# GPS_-_ML8088s.net
KiCad netlist of a schematic drawn in Altium Designer
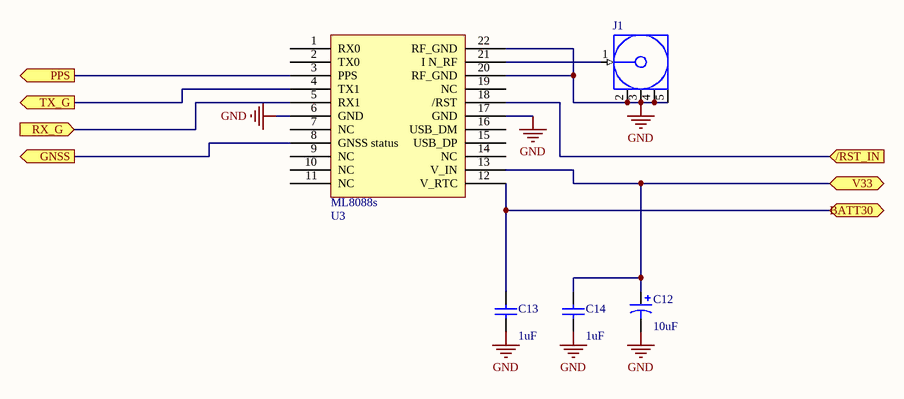
[diagram p0: GPS - ML8088s.SchDoc]

(export (version "E")
  (design (tool "Eeschema 10.0.6"))
  (components
    (comp (ref "C12")
      (value "10uF")
      (footprint "R38")
      (description "Polarized Capacitor (Radial)")
      (fields (field (name "Comment") "Cap Pol1") (field (name "PUBLISHER") "Altium Limited"))
      (libsource (lib "Miscellaneous Devices") (part "Cap Pol1"))
    )
    (comp (ref "C13")
      (value "1uF")
      (footprint "RAD-0.1")
      (description "Capacitor")
      (fields (field (name "Comment") "Cap") (field (name "PUBLISHER") "Altium Limited"))
      (libsource (lib "Miscellaneous Devices") (part "Cap"))
    )
    (comp (ref "C14")
      (value "1uF")
      (footprint "RAD-0.1")
      (description "Capacitor")
      (fields (field (name "Comment") "Cap") (field (name "PUBLISHER") "Altium Limited"))
      (libsource (lib "Miscellaneous Devices") (part "Cap"))
    )
    (comp (ref "J1")
      (value "COAX-F")
      (footprint "MCX5.08-H5")
      (fields (field (name "PUBLISHER") "Altium Limited"))
      (libsource (lib "Miscellaneous Connectors") (part "COAX-F"))
    )
    (comp (ref "U3")
      (value "Component_1")
      (footprint "LCCS127P1300X1500X280-22M")
      (libsource (lib "gps&gsm") (part "Component_1"))
    )
  )
  (nets
    (net (code "1") (name "/BATT30") (class "Default")
      (node (ref "C13") (pin "2") (pinfunction "2_2") (pintype "passive"))
      (node (ref "U3") (pin "12") (pinfunction "V_RTC_12") (pintype "passive"))
    )
    (net (code "2") (name "/GNSS") (class "Default")
      (node (ref "U3") (pin "8") (pinfunction "GNSS_status_8") (pintype "passive"))
    )
    (net (code "3") (name "/PPS") (class "Default")
      (node (ref "U3") (pin "3") (pinfunction "PPS_3") (pintype "passive"))
    )
    (net (code "4") (name "/RX_G") (class "Default")
      (node (ref "U3") (pin "5") (pinfunction "RX1_5") (pintype "passive"))
    )
    (net (code "5") (name "/TX_G") (class "Default")
      (node (ref "U3") (pin "4") (pinfunction "TX1_4") (pintype "passive"))
    )
    (net (code "6") (name "/V33") (class "Default")
      (node (ref "C12") (pin "1") (pinfunction "1_1") (pintype "passive"))
      (node (ref "C14") (pin "2") (pinfunction "2_2") (pintype "passive"))
      (node (ref "U3") (pin "13") (pinfunction "V_IN_13") (pintype "passive"))
    )
    (net (code "7") (name "/{slash}RST_IN") (class "Default")
      (node (ref "U3") (pin "18") (pinfunction "/RST_18") (pintype "passive"))
    )
    (net (code "8") (name "GND") (class "Default")
      (node (ref "C12") (pin "2") (pinfunction "2_2") (pintype "passive"))
      (node (ref "C13") (pin "1") (pinfunction "1_1") (pintype "passive"))
      (node (ref "C14") (pin "1") (pinfunction "1_1") (pintype "passive"))
      (node (ref "J1") (pin "2") (pinfunction "GND_2") (pintype "power_in"))
      (node (ref "J1") (pin "3") (pinfunction "GND_3") (pintype "power_in"))
      (node (ref "J1") (pin "4") (pinfunction "GND_4") (pintype "power_in"))
      (node (ref "J1") (pin "5") (pinfunction "GND_5") (pintype "power_in"))
      (node (ref "U3") (pin "17") (pinfunction "GND_17") (pintype "passive"))
      (node (ref "U3") (pin "20") (pinfunction "RF_GND_20") (pintype "passive"))
      (node (ref "U3") (pin "22") (pinfunction "RF_GND_22") (pintype "passive"))
      (node (ref "U3") (pin "6") (pinfunction "GND_6") (pintype "passive"))
    )
    (net (code "9") (name "Net-(J1-Signal)") (class "Default")
      (node (ref "J1") (pin "1") (pinfunction "Signal_1") (pintype "input"))
      (node (ref "U3") (pin "21") (pinfunction "I_N_RF_21") (pintype "passive"))
    )
    (net (code "10") (name "unconnected-(U3-NC-Pad7)") (class "Default")
      (node (ref "U3") (pin "7") (pinfunction "NC_7") (pintype "passive"))
    )
    (net (code "11") (name "unconnected-(U3-NC-Pad9)") (class "Default")
      (node (ref "U3") (pin "9") (pinfunction "NC_9") (pintype "passive"))
    )
    (net (code "12") (name "unconnected-(U3-NC-Pad10)") (class "Default")
      (node (ref "U3") (pin "10") (pinfunction "NC_10") (pintype "passive"))
    )
    (net (code "13") (name "unconnected-(U3-NC-Pad11)") (class "Default")
      (node (ref "U3") (pin "11") (pinfunction "NC_11") (pintype "passive"))
    )
    (net (code "14") (name "unconnected-(U3-NC-Pad14)") (class "Default")
      (node (ref "U3") (pin "14") (pinfunction "NC_14") (pintype "passive"))
    )
    (net (code "15") (name "unconnected-(U3-NC-Pad19)") (class "Default")
      (node (ref "U3") (pin "19") (pinfunction "NC_19") (pintype "passive"))
    )
    (net (code "16") (name "unconnected-(U3-RX0-Pad1)") (class "Default")
      (node (ref "U3") (pin "1") (pinfunction "RX0_1") (pintype "passive"))
    )
    (net (code "17") (name "unconnected-(U3-TX0-Pad2)") (class "Default")
      (node (ref "U3") (pin "2") (pinfunction "TX0_2") (pintype "passive"))
    )
    (net (code "18") (name "unconnected-(U3-USB_DM-Pad16)") (class "Default")
      (node (ref "U3") (pin "16") (pinfunction "USB_DM_16") (pintype "passive"))
    )
    (net (code "19") (name "unconnected-(U3-USB_DP-Pad15)") (class "Default")
      (node (ref "U3") (pin "15") (pinfunction "USB_DP_15") (pintype "passive"))
    )
  )
)
